# Rover-5_Power_Supply.net
KiCad netlist of a schematic drawn in EAGLE
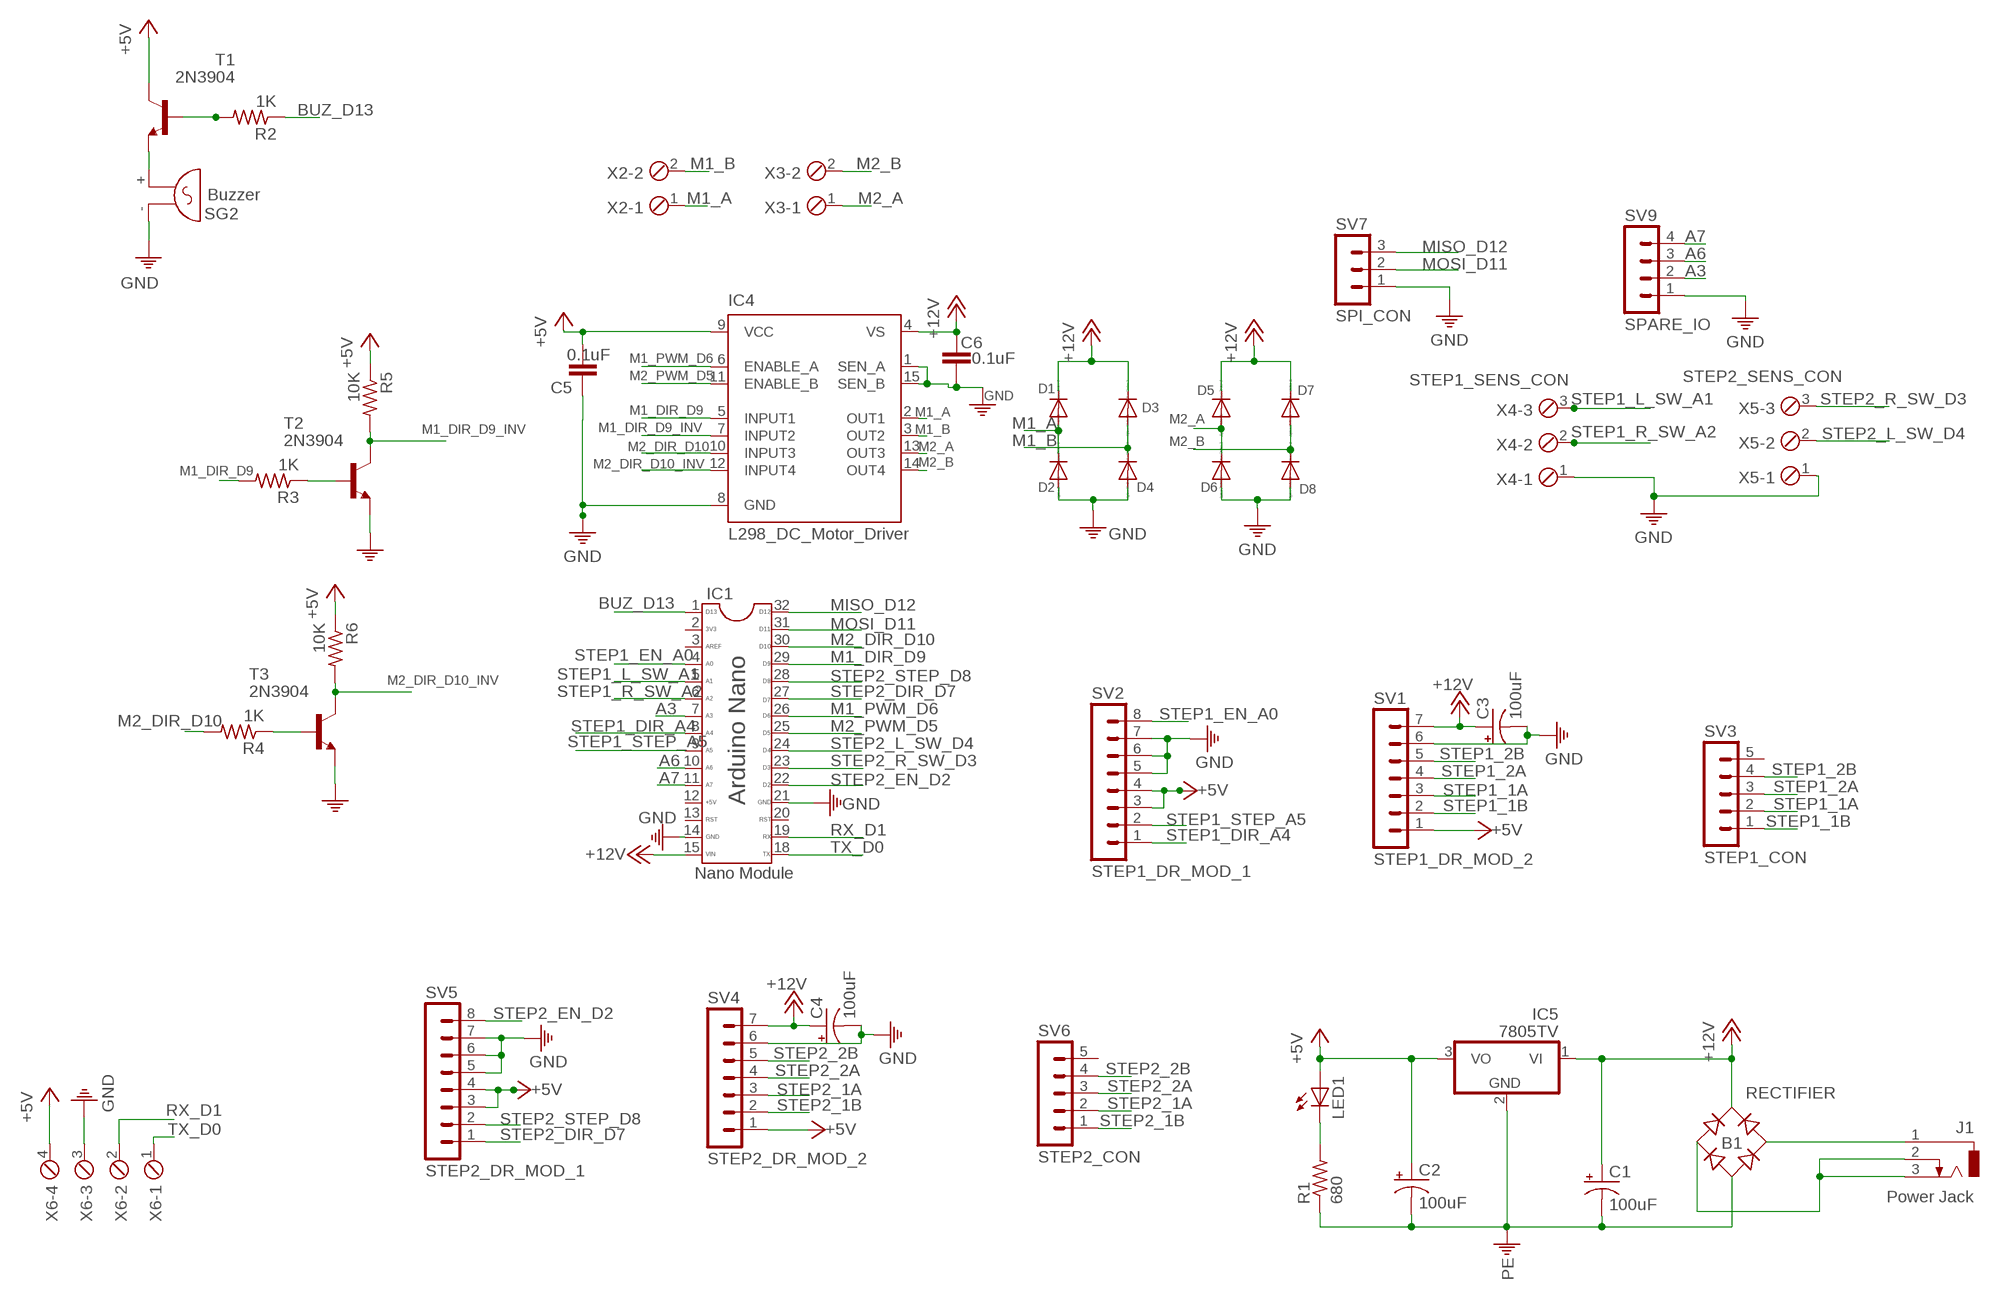
[diagram p0: schematic, sheet 1]

(export (version "E")
  (design (tool "Eeschema 10.0.6"))
  (components
    (comp (ref "B1")
      (value "RECTIFIER")
      (footprint "eagle-import:RB1A")
      (libsource (lib "eagle-import") (part "RB1A"))
    )
    (comp (ref "C1")
      (value "100uF")
      (footprint "eagle-import:E1,8-4")
      (libsource (lib "eagle-import") (part "CPOL-USE1.8-4"))
    )
    (comp (ref "C2")
      (value "100uF")
      (footprint "eagle-import:E1,8-4")
      (libsource (lib "eagle-import") (part "CPOL-USE1.8-4"))
    )
    (comp (ref "C3")
      (value "100uF")
      (footprint "eagle-import:E1,8-4")
      (libsource (lib "eagle-import") (part "CPOL-USE1.8-4"))
    )
    (comp (ref "C4")
      (value "100uF")
      (footprint "eagle-import:E1,8-4")
      (libsource (lib "eagle-import") (part "CPOL-USE1.8-4"))
    )
    (comp (ref "C5")
      (value "0.1uF")
      (footprint "eagle-import:C025-024X044")
      (libsource (lib "eagle-import") (part "C-EU025-024X044"))
    )
    (comp (ref "C6")
      (value "0.1uF")
      (footprint "eagle-import:C025-024X044")
      (libsource (lib "eagle-import") (part "C-EU025-024X044"))
    )
    (comp (ref "D1")
      (value "DIODE-D-2.5")
      (footprint "eagle-import:D-2.5")
      (libsource (lib "eagle-import") (part "DIODE-D-2.5"))
    )
    (comp (ref "D2")
      (value "DIODE-D-2.5")
      (footprint "eagle-import:D-2.5")
      (libsource (lib "eagle-import") (part "DIODE-D-2.5"))
    )
    (comp (ref "D3")
      (value "DIODE-D-2.5")
      (footprint "eagle-import:D-2.5")
      (libsource (lib "eagle-import") (part "DIODE-D-2.5"))
    )
    (comp (ref "D4")
      (value "DIODE-D-2.5")
      (footprint "eagle-import:D-2.5")
      (libsource (lib "eagle-import") (part "DIODE-D-2.5"))
    )
    (comp (ref "D5")
      (value "DIODE-D-2.5")
      (footprint "eagle-import:D-2.5")
      (libsource (lib "eagle-import") (part "DIODE-D-2.5"))
    )
    (comp (ref "D6")
      (value "DIODE-D-2.5")
      (footprint "eagle-import:D-2.5")
      (libsource (lib "eagle-import") (part "DIODE-D-2.5"))
    )
    (comp (ref "D7")
      (value "DIODE-D-2.5")
      (footprint "eagle-import:D-2.5")
      (libsource (lib "eagle-import") (part "DIODE-D-2.5"))
    )
    (comp (ref "D8")
      (value "DIODE-D-2.5")
      (footprint "eagle-import:D-2.5")
      (libsource (lib "eagle-import") (part "DIODE-D-2.5"))
    )
    (comp (ref "IC1")
      (value "Nano Module")
      (footprint "eagle-import:DIL32")
      (libsource (lib "eagle-import") (part "DIL32"))
    )
    (comp (ref "IC4")
      (value "L298_DC_Motor_Driver")
      (footprint "eagle-import:MULTIWATT-15")
      (fields (field (name "MPN") "L298N"))
      (libsource (lib "eagle-import") (part "L298"))
    )
    (comp (ref "IC5")
      (value "7805TV")
      (footprint "eagle-import:TO220V")
      (libsource (lib "eagle-import") (part "78TV05"))
    )
    (comp (ref "J1")
      (value "Power Jack")
      (footprint "eagle-import:ROVER-PW-JACL")
      (libsource (lib "eagle-import") (part "DCJ0303"))
    )
    (comp (ref "LED1")
      (value "LED3MM")
      (footprint "eagle-import:LED3MM")
      (libsource (lib "eagle-import") (part "LED3MM"))
    )
    (comp (ref "R1")
      (value "680")
      (footprint "eagle-import:0204_5")
      (libsource (lib "eagle-import") (part "R-US_0204/5"))
    )
    (comp (ref "R2")
      (value "1K")
      (footprint "eagle-import:0204_5")
      (libsource (lib "eagle-import") (part "R-US_0204/5"))
    )
    (comp (ref "R3")
      (value "1K")
      (footprint "eagle-import:0204_5")
      (libsource (lib "eagle-import") (part "R-US_0204/5"))
    )
    (comp (ref "R4")
      (value "1K")
      (footprint "eagle-import:0204_5")
      (libsource (lib "eagle-import") (part "R-US_0204/5"))
    )
    (comp (ref "R5")
      (value "10K")
      (footprint "eagle-import:0204_5")
      (libsource (lib "eagle-import") (part "R-US_0204/5"))
    )
    (comp (ref "R6")
      (value "10K")
      (footprint "eagle-import:0204_5")
      (libsource (lib "eagle-import") (part "R-US_0204/5"))
    )
    (comp (ref "SG2")
      (value "Buzzer")
      (footprint "eagle-import:F_QMX")
      (libsource (lib "eagle-import") (part "F/QMX"))
    )
    (comp (ref "SV1")
      (value "STEP1_DR_MOD_2")
      (footprint "eagle-import:MA07-1")
      (libsource (lib "eagle-import") (part "MA07-1"))
    )
    (comp (ref "SV2")
      (value "STEP1_DR_MOD_1")
      (footprint "eagle-import:MA08-1")
      (libsource (lib "eagle-import") (part "MA08-1"))
    )
    (comp (ref "SV3")
      (value "STEP1_CON")
      (footprint "eagle-import:MA05-1")
      (libsource (lib "eagle-import") (part "MA05-1"))
    )
    (comp (ref "SV4")
      (value "STEP2_DR_MOD_2")
      (footprint "eagle-import:MA07-1")
      (libsource (lib "eagle-import") (part "MA07-1"))
    )
    (comp (ref "SV5")
      (value "STEP2_DR_MOD_1")
      (footprint "eagle-import:MA08-1")
      (libsource (lib "eagle-import") (part "MA08-1"))
    )
    (comp (ref "SV6")
      (value "STEP2_CON")
      (footprint "eagle-import:MA05-1")
      (libsource (lib "eagle-import") (part "MA05-1"))
    )
    (comp (ref "SV7")
      (value "SPI_CON")
      (footprint "eagle-import:MA03-1")
      (libsource (lib "eagle-import") (part "MA03-1"))
    )
    (comp (ref "SV9")
      (value "SPARE_IO")
      (footprint "eagle-import:MA04-1")
      (libsource (lib "eagle-import") (part "MA04-1"))
    )
    (comp (ref "T1")
      (value "2N3904")
      (footprint "eagle-import:TO92")
      (libsource (lib "eagle-import") (part "2N3904"))
    )
    (comp (ref "T2")
      (value "2N3904")
      (footprint "eagle-import:TO92")
      (libsource (lib "eagle-import") (part "2N3904"))
    )
    (comp (ref "T3")
      (value "2N3904")
      (footprint "eagle-import:TO92")
      (libsource (lib "eagle-import") (part "2N3904"))
    )
    (comp (ref "X2")
      (value "MPT2")
      (footprint "eagle-import:2POL254")
      (libsource (lib "eagle-import") (part "MPT2"))
    )
    (comp (ref "X3")
      (value "MPT2")
      (footprint "eagle-import:2POL254")
      (libsource (lib "eagle-import") (part "MPT2"))
    )
    (comp (ref "X4")
      (value "STEP1_SENS_CON")
      (footprint "eagle-import:3POL254")
      (libsource (lib "eagle-import") (part "MPT3"))
    )
    (comp (ref "X5")
      (value "STEP2_SENS_CON")
      (footprint "eagle-import:3POL254")
      (libsource (lib "eagle-import") (part "MPT3"))
    )
    (comp (ref "X6")
      (value "MPT4")
      (footprint "eagle-import:4POL254")
      (libsource (lib "eagle-import") (part "MPT4"))
    )
  )
  (nets
    (net (code "1") (name "+5V") (class "Default")
      (node (ref "C2") (pin "+") (pinfunction "+_+") (pintype "passive"))
      (node (ref "C5") (pin "2") (pinfunction "2_2") (pintype "passive"))
      (node (ref "IC4") (pin "9") (pinfunction "VCC_9") (pintype "power_in"))
      (node (ref "IC5") (pin "3") (pinfunction "VO_3") (pintype "passive"))
      (node (ref "LED1") (pin "A") (pinfunction "A_A") (pintype "passive"))
      (node (ref "R5") (pin "1") (pinfunction "1_1") (pintype "passive"))
      (node (ref "R6") (pin "1") (pinfunction "1_1") (pintype "passive"))
      (node (ref "SV1") (pin "1") (pinfunction "1_1") (pintype "passive"))
      (node (ref "SV2") (pin "3") (pinfunction "3_3") (pintype "passive"))
      (node (ref "SV2") (pin "4") (pinfunction "4_4") (pintype "passive"))
      (node (ref "SV4") (pin "1") (pinfunction "1_1") (pintype "passive"))
      (node (ref "SV5") (pin "3") (pinfunction "3_3") (pintype "passive"))
      (node (ref "SV5") (pin "4") (pinfunction "4_4") (pintype "passive"))
      (node (ref "T1") (pin "1") (pinfunction "C_1") (pintype "passive"))
      (node (ref "X6") (pin "4") (pinfunction "1_4") (pintype "passive"))
    )
    (net (code "2") (name "+12V") (class "Default")
      (node (ref "B1") (pin "+") (pinfunction "+_+") (pintype "passive"))
      (node (ref "C1") (pin "+") (pinfunction "+_+") (pintype "passive"))
      (node (ref "C3") (pin "+") (pinfunction "+_+") (pintype "passive"))
      (node (ref "C4") (pin "+") (pinfunction "+_+") (pintype "passive"))
      (node (ref "C6") (pin "2") (pinfunction "2_2") (pintype "passive"))
      (node (ref "D1") (pin "C") (pinfunction "C_C") (pintype "passive"))
      (node (ref "D3") (pin "C") (pinfunction "C_C") (pintype "passive"))
      (node (ref "D5") (pin "C") (pinfunction "C_C") (pintype "passive"))
      (node (ref "D7") (pin "C") (pinfunction "C_C") (pintype "passive"))
      (node (ref "IC1") (pin "15") (pinfunction "VIN_15") (pintype "passive"))
      (node (ref "IC4") (pin "4") (pinfunction "VS_4") (pintype "power_in"))
      (node (ref "IC5") (pin "1") (pinfunction "VI_1") (pintype "input"))
      (node (ref "SV1") (pin "7") (pinfunction "7_7") (pintype "passive"))
      (node (ref "SV4") (pin "7") (pinfunction "7_7") (pintype "passive"))
    )
    (net (code "3") (name "/A3") (class "Default")
      (node (ref "IC1") (pin "7") (pinfunction "A3/D17_7") (pintype "passive"))
      (node (ref "SV9") (pin "2") (pinfunction "2_2") (pintype "passive"))
    )
    (net (code "4") (name "/A6") (class "Default")
      (node (ref "IC1") (pin "10") (pinfunction "A6_10") (pintype "passive"))
      (node (ref "SV9") (pin "3") (pinfunction "3_3") (pintype "passive"))
    )
    (net (code "5") (name "/A7") (class "Default")
      (node (ref "IC1") (pin "11") (pinfunction "A7_11") (pintype "passive"))
      (node (ref "SV9") (pin "4") (pinfunction "4_4") (pintype "passive"))
    )
    (net (code "6") (name "/BUZ_D13") (class "Default")
      (node (ref "IC1") (pin "1") (pinfunction "D13_1") (pintype "passive"))
      (node (ref "R2") (pin "1") (pinfunction "1_1") (pintype "passive"))
    )
    (net (code "7") (name "/M1_A") (class "Default")
      (node (ref "D1") (pin "A") (pinfunction "A_A") (pintype "passive"))
      (node (ref "D2") (pin "C") (pinfunction "C_C") (pintype "passive"))
      (node (ref "IC4") (pin "2") (pinfunction "OUT1_2") (pintype "output"))
      (node (ref "X2") (pin "1") (pinfunction "1_1") (pintype "passive"))
    )
    (net (code "8") (name "/M1_B") (class "Default")
      (node (ref "D3") (pin "A") (pinfunction "A_A") (pintype "passive"))
      (node (ref "D4") (pin "C") (pinfunction "C_C") (pintype "passive"))
      (node (ref "IC4") (pin "3") (pinfunction "OUT2_3") (pintype "output"))
      (node (ref "X2") (pin "2") (pinfunction "1_2") (pintype "passive"))
    )
    (net (code "9") (name "/M1_DIR_D9") (class "Default")
      (node (ref "IC1") (pin "29") (pinfunction "D9/PWM_29") (pintype "passive"))
      (node (ref "IC4") (pin "5") (pinfunction "INPUT1_5") (pintype "input"))
      (node (ref "R3") (pin "2") (pinfunction "2_2") (pintype "passive"))
    )
    (net (code "10") (name "/M1_DIR_D9_INV") (class "Default")
      (node (ref "IC4") (pin "7") (pinfunction "INPUT2_7") (pintype "input"))
      (node (ref "R5") (pin "2") (pinfunction "2_2") (pintype "passive"))
      (node (ref "T2") (pin "1") (pinfunction "C_1") (pintype "passive"))
    )
    (net (code "11") (name "/M1_PWM_D6") (class "Default")
      (node (ref "IC1") (pin "26") (pinfunction "D6/PWM_26") (pintype "passive"))
      (node (ref "IC4") (pin "6") (pinfunction "ENABLE_A_6") (pintype "input"))
    )
    (net (code "12") (name "/M2_A") (class "Default")
      (node (ref "D5") (pin "A") (pinfunction "A_A") (pintype "passive"))
      (node (ref "D6") (pin "C") (pinfunction "C_C") (pintype "passive"))
      (node (ref "IC4") (pin "13") (pinfunction "OUT3_13") (pintype "output"))
      (node (ref "X3") (pin "1") (pinfunction "1_1") (pintype "passive"))
    )
    (net (code "13") (name "/M2_B") (class "Default")
      (node (ref "D7") (pin "A") (pinfunction "A_A") (pintype "passive"))
      (node (ref "D8") (pin "C") (pinfunction "C_C") (pintype "passive"))
      (node (ref "IC4") (pin "14") (pinfunction "OUT4_14") (pintype "output"))
      (node (ref "X3") (pin "2") (pinfunction "1_2") (pintype "passive"))
    )
    (net (code "14") (name "/M2_DIR_D10") (class "Default")
      (node (ref "IC1") (pin "30") (pinfunction "D10/PWM_30") (pintype "passive"))
      (node (ref "IC4") (pin "10") (pinfunction "INPUT3_10") (pintype "input"))
      (node (ref "R4") (pin "2") (pinfunction "2_2") (pintype "passive"))
    )
    (net (code "15") (name "/M2_DIR_D10_INV") (class "Default")
      (node (ref "IC4") (pin "12") (pinfunction "INPUT4_12") (pintype "input"))
      (node (ref "R6") (pin "2") (pinfunction "2_2") (pintype "passive"))
      (node (ref "T3") (pin "1") (pinfunction "C_1") (pintype "passive"))
    )
    (net (code "16") (name "/M2_PWM_D5") (class "Default")
      (node (ref "IC1") (pin "25") (pinfunction "D5/PWM_25") (pintype "passive"))
      (node (ref "IC4") (pin "11") (pinfunction "ENABLE_B_11") (pintype "input"))
    )
    (net (code "17") (name "/MISO_D12") (class "Default")
      (node (ref "IC1") (pin "32") (pinfunction "D12/MISO_32") (pintype "passive"))
      (node (ref "SV7") (pin "3") (pinfunction "3_3") (pintype "passive"))
    )
    (net (code "18") (name "/MOSI_D11") (class "Default")
      (node (ref "IC1") (pin "31") (pinfunction "D11/MOSI_31") (pintype "passive"))
      (node (ref "SV7") (pin "2") (pinfunction "2_2") (pintype "passive"))
    )
    (net (code "19") (name "/RX_D1") (class "Default")
      (node (ref "IC1") (pin "19") (pinfunction "RX_19") (pintype "passive"))
      (node (ref "X6") (pin "2") (pinfunction "1_2") (pintype "passive"))
    )
    (net (code "20") (name "/STEP1_1A") (class "Default")
      (node (ref "SV1") (pin "3") (pinfunction "3_3") (pintype "passive"))
      (node (ref "SV3") (pin "2") (pinfunction "2_2") (pintype "passive"))
    )
    (net (code "21") (name "/STEP1_1B") (class "Default")
      (node (ref "SV1") (pin "2") (pinfunction "2_2") (pintype "passive"))
      (node (ref "SV3") (pin "1") (pinfunction "1_1") (pintype "passive"))
    )
    (net (code "22") (name "/STEP1_2A") (class "Default")
      (node (ref "SV1") (pin "4") (pinfunction "4_4") (pintype "passive"))
      (node (ref "SV3") (pin "3") (pinfunction "3_3") (pintype "passive"))
    )
    (net (code "23") (name "/STEP1_2B") (class "Default")
      (node (ref "SV1") (pin "5") (pinfunction "5_5") (pintype "passive"))
      (node (ref "SV3") (pin "4") (pinfunction "4_4") (pintype "passive"))
    )
    (net (code "24") (name "/STEP1_DIR_A4") (class "Default")
      (node (ref "IC1") (pin "8") (pinfunction "A4/D18/SDA_8") (pintype "passive"))
      (node (ref "SV2") (pin "1") (pinfunction "1_1") (pintype "passive"))
    )
    (net (code "25") (name "/STEP1_EN_A0") (class "Default")
      (node (ref "IC1") (pin "4") (pinfunction "A0/D14_4") (pintype "passive"))
      (node (ref "SV2") (pin "8") (pinfunction "8_8") (pintype "passive"))
    )
    (net (code "26") (name "/STEP1_L_SW_A1") (class "Default")
      (node (ref "IC1") (pin "5") (pinfunction "A1/D15_5") (pintype "passive"))
      (node (ref "X4") (pin "3") (pinfunction "1_3") (pintype "passive"))
    )
    (net (code "27") (name "/STEP1_R_SW_A2") (class "Default")
      (node (ref "IC1") (pin "6") (pinfunction "A2/D16_6") (pintype "passive"))
      (node (ref "X4") (pin "2") (pinfunction "1_2") (pintype "passive"))
    )
    (net (code "28") (name "/STEP1_STEP_A5") (class "Default")
      (node (ref "IC1") (pin "9") (pinfunction "A5/D19/SCL_9") (pintype "passive"))
      (node (ref "SV2") (pin "2") (pinfunction "2_2") (pintype "passive"))
    )
    (net (code "29") (name "/STEP2_1A") (class "Default")
      (node (ref "SV4") (pin "3") (pinfunction "3_3") (pintype "passive"))
      (node (ref "SV6") (pin "2") (pinfunction "2_2") (pintype "passive"))
    )
    (net (code "30") (name "/STEP2_1B") (class "Default")
      (node (ref "SV4") (pin "2") (pinfunction "2_2") (pintype "passive"))
      (node (ref "SV6") (pin "1") (pinfunction "1_1") (pintype "passive"))
    )
    (net (code "31") (name "/STEP2_2A") (class "Default")
      (node (ref "SV4") (pin "4") (pinfunction "4_4") (pintype "passive"))
      (node (ref "SV6") (pin "3") (pinfunction "3_3") (pintype "passive"))
    )
    (net (code "32") (name "/STEP2_2B") (class "Default")
      (node (ref "SV4") (pin "5") (pinfunction "5_5") (pintype "passive"))
      (node (ref "SV6") (pin "4") (pinfunction "4_4") (pintype "passive"))
    )
    (net (code "33") (name "/STEP2_DIR_D7") (class "Default")
      (node (ref "IC1") (pin "27") (pinfunction "D7_27") (pintype "passive"))
      (node (ref "SV5") (pin "1") (pinfunction "1_1") (pintype "passive"))
    )
    (net (code "34") (name "/STEP2_EN_D2") (class "Default")
      (node (ref "IC1") (pin "22") (pinfunction "D2_22") (pintype "passive"))
      (node (ref "SV5") (pin "8") (pinfunction "8_8") (pintype "passive"))
    )
    (net (code "35") (name "/STEP2_L_SW_D4") (class "Default")
      (node (ref "IC1") (pin "24") (pinfunction "D4_24") (pintype "passive"))
      (node (ref "X5") (pin "2") (pinfunction "1_2") (pintype "passive"))
    )
    (net (code "36") (name "/STEP2_R_SW_D3") (class "Default")
      (node (ref "IC1") (pin "23") (pinfunction "D3_23") (pintype "passive"))
      (node (ref "X5") (pin "3") (pinfunction "1_3") (pintype "passive"))
    )
    (net (code "37") (name "/STEP2_STEP_D8") (class "Default")
      (node (ref "IC1") (pin "28") (pinfunction "D8_28") (pintype "passive"))
      (node (ref "SV5") (pin "2") (pinfunction "2_2") (pintype "passive"))
    )
    (net (code "38") (name "/TX_D0") (class "Default")
      (node (ref "IC1") (pin "18") (pinfunction "TX_18") (pintype "passive"))
      (node (ref "X6") (pin "1") (pinfunction "1_1") (pintype "passive"))
    )
    (net (code "39") (name "GND") (class "Default")
      (node (ref "B1") (pin "-") (pinfunction "-_-") (pintype "passive"))
      (node (ref "C1") (pin "-") (pinfunction "-_-") (pintype "passive"))
      (node (ref "C2") (pin "-") (pinfunction "-_-") (pintype "passive"))
      (node (ref "C3") (pin "-") (pinfunction "-_-") (pintype "passive"))
      (node (ref "C4") (pin "-") (pinfunction "-_-") (pintype "passive"))
      (node (ref "C5") (pin "1") (pinfunction "1_1") (pintype "passive"))
      (node (ref "C6") (pin "1") (pinfunction "1_1") (pintype "passive"))
      (node (ref "D2") (pin "A") (pinfunction "A_A") (pintype "passive"))
      (node (ref "D4") (pin "A") (pinfunction "A_A") (pintype "passive"))
      (node (ref "D6") (pin "A") (pinfunction "A_A") (pintype "passive"))
      (node (ref "D8") (pin "A") (pinfunction "A_A") (pintype "passive"))
      (node (ref "IC1") (pin "14") (pinfunction "GND1_14") (pintype "passive"))
      (node (ref "IC1") (pin "21") (pinfunction "GND2_21") (pintype "passive"))
      (node (ref "IC4") (pin "1") (pinfunction "SEN_A_1") (pintype "input"))
      (node (ref "IC4") (pin "15") (pinfunction "SEN_B_15") (pintype "input"))
      (node (ref "IC4") (pin "8") (pinfunction "GND_8") (pintype "power_in"))
      (node (ref "IC5") (pin "2") (pinfunction "GND_2") (pintype "passive"))
      (node (ref "R1") (pin "1") (pinfunction "1_1") (pintype "passive"))
      (node (ref "SG2") (pin "-") (pinfunction "1_-") (pintype "passive"))
      (node (ref "SV1") (pin "6") (pinfunction "6_6") (pintype "passive"))
      (node (ref "SV2") (pin "5") (pinfunction "5_5") (pintype "passive"))
      (node (ref "SV2") (pin "6") (pinfunction "6_6") (pintype "passive"))
      (node (ref "SV2") (pin "7") (pinfunction "7_7") (pintype "passive"))
      (node (ref "SV4") (pin "6") (pinfunction "6_6") (pintype "passive"))
      (node (ref "SV5") (pin "5") (pinfunction "5_5") (pintype "passive"))
      (node (ref "SV5") (pin "6") (pinfunction "6_6") (pintype "passive"))
      (node (ref "SV5") (pin "7") (pinfunction "7_7") (pintype "passive"))
      (node (ref "SV7") (pin "1") (pinfunction "1_1") (pintype "passive"))
      (node (ref "SV9") (pin "1") (pinfunction "1_1") (pintype "passive"))
      (node (ref "T2") (pin "3") (pinfunction "E_3") (pintype "passive"))
      (node (ref "T3") (pin "3") (pinfunction "E_3") (pintype "passive"))
      (node (ref "X4") (pin "1") (pinfunction "1_1") (pintype "passive"))
      (node (ref "X5") (pin "1") (pinfunction "1_1") (pintype "passive"))
      (node (ref "X6") (pin "3") (pinfunction "1_3") (pintype "passive"))
    )
    (net (code "40") (name "Net-(B1-PadAC1)") (class "Default")
      (node (ref "B1") (pin "AC1") (pinfunction "AC1_AC1") (pintype "passive"))
      (node (ref "J1") (pin "1") (pinfunction "1_1") (pintype "passive"))
    )
    (net (code "41") (name "Net-(B1-PadAC2)") (class "Default")
      (node (ref "B1") (pin "AC2") (pinfunction "AC2_AC2") (pintype "passive"))
      (node (ref "J1") (pin "2") (pinfunction "2_2") (pintype "passive"))
      (node (ref "J1") (pin "3") (pinfunction "3_3") (pintype "passive"))
    )
    (net (code "42") (name "Net-(LED1-C)") (class "Default")
      (node (ref "LED1") (pin "K") (pinfunction "C_K") (pintype "passive"))
      (node (ref "R1") (pin "2") (pinfunction "2_2") (pintype "passive"))
    )
    (net (code "43") (name "Net-(SG2-2)") (class "Default")
      (node (ref "SG2") (pin "+") (pinfunction "2_+") (pintype "passive"))
      (node (ref "T1") (pin "3") (pinfunction "E_3") (pintype "passive"))
    )
    (net (code "44") (name "Net-(T1-B)") (class "Default")
      (node (ref "R2") (pin "2") (pinfunction "2_2") (pintype "passive"))
      (node (ref "T1") (pin "2") (pinfunction "B_2") (pintype "passive"))
    )
    (net (code "45") (name "Net-(T2-B)") (class "Default")
      (node (ref "R3") (pin "1") (pinfunction "1_1") (pintype "passive"))
      (node (ref "T2") (pin "2") (pinfunction "B_2") (pintype "passive"))
    )
    (net (code "46") (name "Net-(T3-B)") (class "Default")
      (node (ref "R4") (pin "1") (pinfunction "1_1") (pintype "passive"))
      (node (ref "T3") (pin "2") (pinfunction "B_2") (pintype "passive"))
    )
    (net (code "47") (name "unconnected-(IC1-3V3-Pad2)") (class "Default")
      (node (ref "IC1") (pin "2") (pinfunction "3V3_2") (pintype "passive"))
    )
    (net (code "48") (name "unconnected-(IC1-5V-Pad12)") (class "Default")
      (node (ref "IC1") (pin "12") (pinfunction "5V_12") (pintype "passive"))
    )
    (net (code "49") (name "unconnected-(IC1-AREF-Pad3)") (class "Default")
      (node (ref "IC1") (pin "3") (pinfunction "AREF_3") (pintype "passive"))
    )
    (net (code "50") (name "unconnected-(IC1-RST1-Pad13)") (class "Default")
      (node (ref "IC1") (pin "13") (pinfunction "RST1_13") (pintype "passive"))
    )
    (net (code "51") (name "unconnected-(IC1-RST2-Pad20)") (class "Default")
      (node (ref "IC1") (pin "20") (pinfunction "RST2_20") (pintype "passive"))
    )
    (net (code "52") (name "unconnected-(SV3-Pad5)") (class "Default")
      (node (ref "SV3") (pin "5") (pinfunction "5_5") (pintype "passive"))
    )
    (net (code "53") (name "unconnected-(SV6-Pad5)") (class "Default")
      (node (ref "SV6") (pin "5") (pinfunction "5_5") (pintype "passive"))
    )
  )
)
